# 4__eth1.net
KiCad netlist of a schematic drawn in Altium Designer
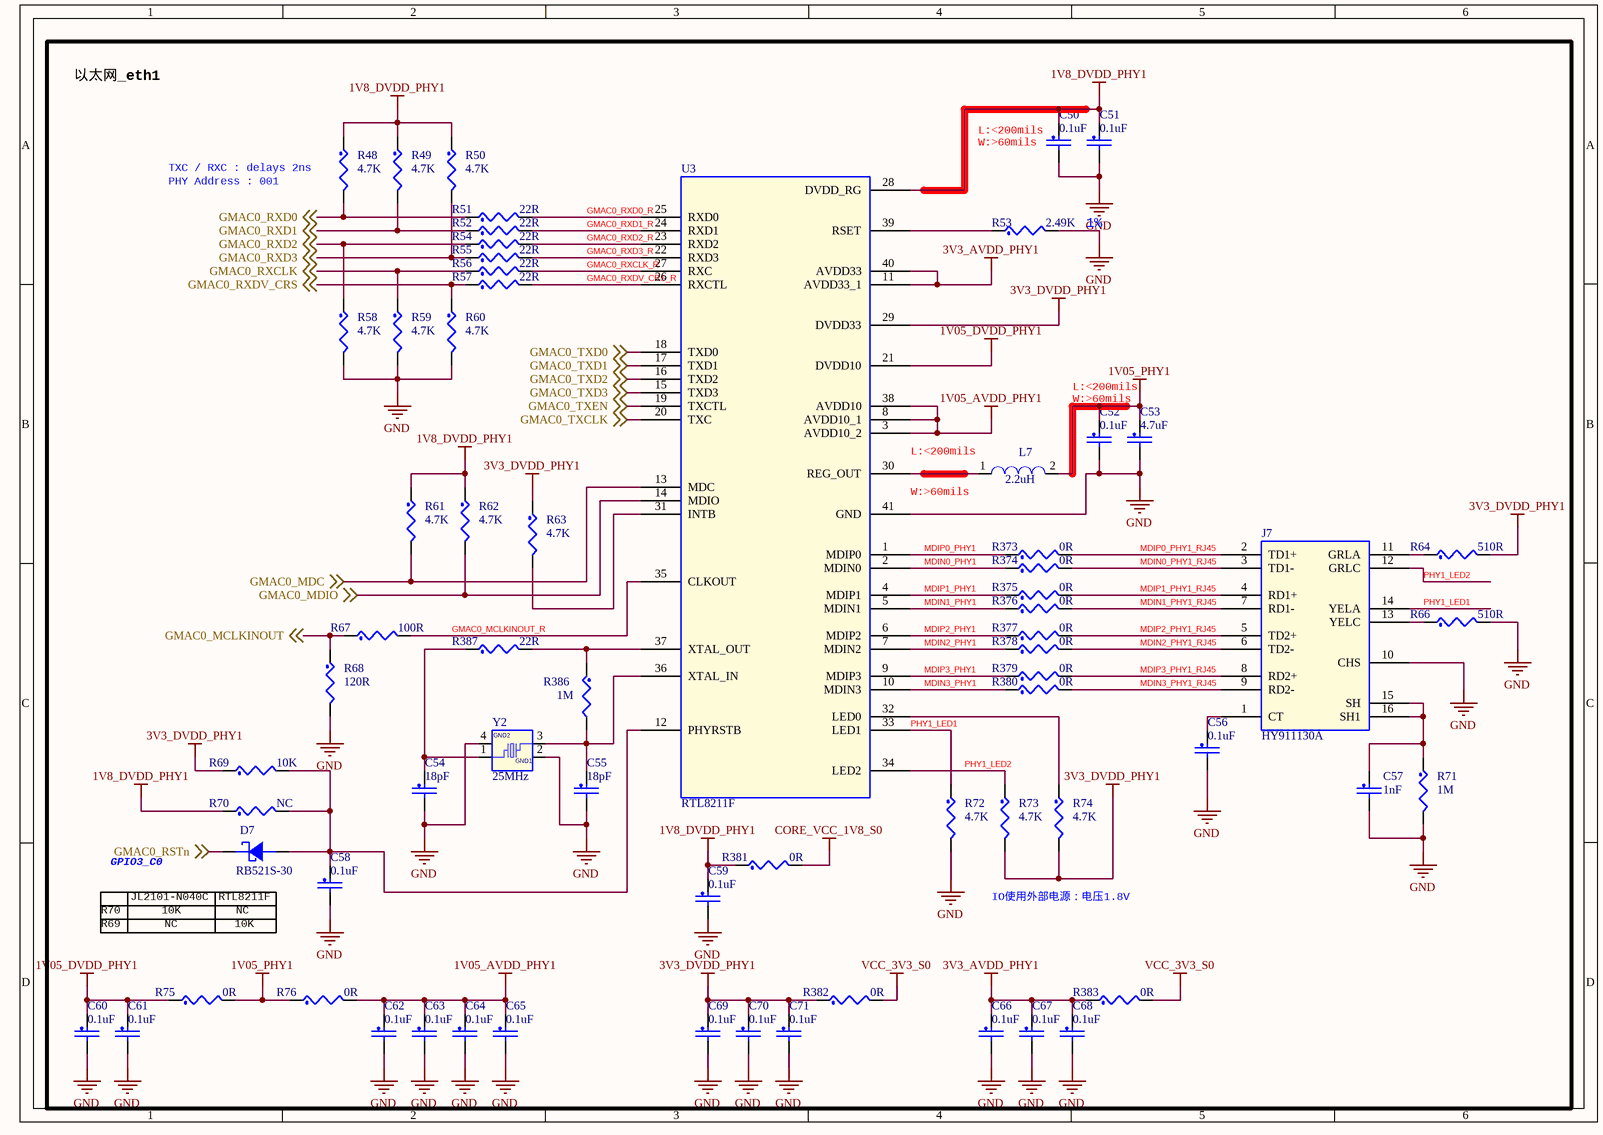
[diagram p0: 4.以太网_eth1.SchDoc]

(export (version "E")
  (design (tool "Eeschema 10.0.6"))
  (components
    (comp (ref "C50") (value "0.1uF") (footprint "0.PCB1:C0402") (libsource (lib "RK3588底板") (part "CAP_NP")))
    (comp (ref "C51") (value "0.1uF") (footprint "0.PCB1:C0402") (libsource (lib "RK3588底板") (part "CAP_NP")))
    (comp (ref "C52") (value "0.1uF") (footprint "0.PCB1:C0402") (libsource (lib "RK3588底板") (part "CAP_NP")))
    (comp (ref "C53") (value "4.7uF") (footprint "0.PCB1:C0402") (libsource (lib "RK3588底板") (part "CAP_NP")))
    (comp (ref "C54") (value "18pF") (footprint "0.PCB1:C0402") (libsource (lib "RK3588底板") (part "CAP_NP")))
    (comp (ref "C55") (value "18pF") (footprint "0.PCB1:C0402") (libsource (lib "RK3588底板") (part "CAP_NP")))
    (comp (ref "C56") (value "0.1uF") (footprint "0.PCB1:C0402") (libsource (lib "RK3588底板") (part "CAP_NP")))
    (comp (ref "C57") (value "1nF") (footprint "0.PCB1:C0805") (libsource (lib "RK3588底板") (part "CAP_NP")))
    (comp (ref "C58") (value "0.1uF") (footprint "0.PCB1:C0402") (libsource (lib "RK3588底板") (part "CAP_NP")))
    (comp (ref "C59") (value "0.1uF") (footprint "0.PCB1:C0402") (libsource (lib "RK3588底板") (part "CAP_NP")))
    (comp (ref "C60") (value "0.1uF") (footprint "0.PCB1:C0402") (libsource (lib "RK3588底板") (part "CAP_NP")))
    (comp (ref "C61") (value "0.1uF") (footprint "0.PCB1:C0402") (libsource (lib "RK3588底板") (part "CAP_NP")))
    (comp (ref "C62") (value "0.1uF") (footprint "0.PCB1:C0402") (libsource (lib "RK3588底板") (part "CAP_NP")))
    (comp (ref "C63") (value "0.1uF") (footprint "0.PCB1:C0402") (libsource (lib "RK3588底板") (part "CAP_NP")))
    (comp (ref "C64") (value "0.1uF") (footprint "0.PCB1:C0402") (libsource (lib "RK3588底板") (part "CAP_NP")))
    (comp (ref "C65") (value "0.1uF") (footprint "0.PCB1:C0402") (libsource (lib "RK3588底板") (part "CAP_NP")))
    (comp (ref "C66") (value "0.1uF") (footprint "0.PCB1:C0402") (libsource (lib "RK3588底板") (part "CAP_NP")))
    (comp (ref "C67") (value "0.1uF") (footprint "0.PCB1:C0402") (libsource (lib "RK3588底板") (part "CAP_NP")))
    (comp (ref "C68") (value "0.1uF") (footprint "0.PCB1:C0402") (libsource (lib "RK3588底板") (part "CAP_NP")))
    (comp (ref "C69") (value "0.1uF") (footprint "0.PCB1:C0402") (libsource (lib "RK3588底板") (part "CAP_NP")))
    (comp (ref "C70") (value "0.1uF") (footprint "0.PCB1:C0402") (libsource (lib "RK3588底板") (part "CAP_NP")))
    (comp (ref "C71") (value "0.1uF") (footprint "0.PCB1:C0402") (libsource (lib "RK3588底板") (part "CAP_NP")))
    (comp (ref "D7")
      (value "RB521S-30")
      (footprint "0.PCB1:SOD523")
      (libsource (lib "RK3588底板") (part "DIODE_SCHTKY"))
    )
    (comp (ref "J7")
      (value "HY911130A")
      (footprint "0.PCB1:HY911130A")
      (libsource (lib "RK3588底板") (part "HY911130A"))
    )
    (comp (ref "L7") (value "2.2uH") (footprint "0.PCB1:L2520") (libsource (lib "RK3588底板") (part "IND")))
    (comp (ref "R48") (value "4.7K") (footprint "0.PCB1:R0402") (libsource (lib "RK3588底板") (part "RES")))
    (comp (ref "R49") (value "4.7K") (footprint "0.PCB1:R0402") (libsource (lib "RK3588底板") (part "RES")))
    (comp (ref "R50") (value "4.7K") (footprint "0.PCB1:R0402") (libsource (lib "RK3588底板") (part "RES")))
    (comp (ref "R51") (value "22R") (footprint "0.PCB1:R0402") (libsource (lib "RK3588底板") (part "RES")))
    (comp (ref "R52") (value "22R") (footprint "0.PCB1:R0402") (libsource (lib "RK3588底板") (part "RES")))
    (comp (ref "R53") (value "2.49K") (footprint "0.PCB1:R0402") (libsource (lib "RK3588底板") (part "RES")))
    (comp (ref "R54") (value "22R") (footprint "0.PCB1:R0402") (libsource (lib "RK3588底板") (part "RES")))
    (comp (ref "R55") (value "22R") (footprint "0.PCB1:R0402") (libsource (lib "RK3588底板") (part "RES")))
    (comp (ref "R56") (value "22R") (footprint "0.PCB1:R0402") (libsource (lib "RK3588底板") (part "RES")))
    (comp (ref "R57") (value "22R") (footprint "0.PCB1:R0402") (libsource (lib "RK3588底板") (part "RES")))
    (comp (ref "R58") (value "4.7K") (footprint "0.PCB1:R0402") (libsource (lib "RK3588底板") (part "RES")))
    (comp (ref "R59") (value "4.7K") (footprint "0.PCB1:R0402") (libsource (lib "RK3588底板") (part "RES")))
    (comp (ref "R60") (value "4.7K") (footprint "0.PCB1:R0402") (libsource (lib "RK3588底板") (part "RES")))
    (comp (ref "R61") (value "4.7K") (footprint "0.PCB1:R0402") (libsource (lib "RK3588底板") (part "RES")))
    (comp (ref "R62") (value "4.7K") (footprint "0.PCB1:R0402") (libsource (lib "RK3588底板") (part "RES")))
    (comp (ref "R63") (value "4.7K") (footprint "0.PCB1:R0402") (libsource (lib "RK3588底板") (part "RES")))
    (comp (ref "R64") (value "510R") (footprint "0.PCB1:R0603") (libsource (lib "RK3588底板") (part "RES")))
    (comp (ref "R66") (value "510R") (footprint "0.PCB1:R0603") (libsource (lib "RK3588底板") (part "RES")))
    (comp (ref "R67") (value "100R") (footprint "0.PCB1:R0402") (libsource (lib "RK3588底板") (part "RES")))
    (comp (ref "R68") (value "120R") (footprint "0.PCB1:R0402") (libsource (lib "RK3588底板") (part "RES")))
    (comp (ref "R69") (value "10K") (footprint "0.PCB1:R0402") (libsource (lib "RK3588底板") (part "RES")))
    (comp (ref "R70") (value "NC") (footprint "0.PCB1:R0402") (libsource (lib "RK3588底板") (part "RES")))
    (comp (ref "R71") (value "1M") (footprint "0.PCB1:R0805") (libsource (lib "RK3588底板") (part "RES")))
    (comp (ref "R72") (value "4.7K") (footprint "0.PCB1:R0402") (libsource (lib "RK3588底板") (part "RES")))
    (comp (ref "R73") (value "4.7K") (footprint "0.PCB1:R0402") (libsource (lib "RK3588底板") (part "RES")))
    (comp (ref "R74") (value "4.7K") (footprint "0.PCB1:R0402") (libsource (lib "RK3588底板") (part "RES")))
    (comp (ref "R75") (value "0R") (footprint "0.PCB1:R0402") (libsource (lib "RK3588底板") (part "RES")))
    (comp (ref "R76") (value "0R") (footprint "0.PCB1:R0402") (libsource (lib "RK3588底板") (part "RES")))
    (comp (ref "R373") (value "0R") (footprint "0.PCB1:R0201") (libsource (lib "RK3588底板") (part "RES")))
    (comp (ref "R374") (value "0R") (footprint "0.PCB1:R0201") (libsource (lib "RK3588底板") (part "RES")))
    (comp (ref "R375") (value "0R") (footprint "0.PCB1:R0201") (libsource (lib "RK3588底板") (part "RES")))
    (comp (ref "R376") (value "0R") (footprint "0.PCB1:R0201") (libsource (lib "RK3588底板") (part "RES")))
    (comp (ref "R377") (value "0R") (footprint "0.PCB1:R0201") (libsource (lib "RK3588底板") (part "RES")))
    (comp (ref "R378") (value "0R") (footprint "0.PCB1:R0201") (libsource (lib "RK3588底板") (part "RES")))
    (comp (ref "R379") (value "0R") (footprint "0.PCB1:R0201") (libsource (lib "RK3588底板") (part "RES")))
    (comp (ref "R380") (value "0R") (footprint "0.PCB1:R0201") (libsource (lib "RK3588底板") (part "RES")))
    (comp (ref "R381") (value "0R") (footprint "0.PCB1:R0402") (libsource (lib "RK3588底板") (part "RES")))
    (comp (ref "R382") (value "0R") (footprint "0.PCB1:R0402") (libsource (lib "RK3588底板") (part "RES")))
    (comp (ref "R383") (value "0R") (footprint "0.PCB1:R0402") (libsource (lib "RK3588底板") (part "RES")))
    (comp (ref "R386") (value "1M") (footprint "0.PCB1:R0402") (libsource (lib "RK3588底板") (part "RES")))
    (comp (ref "R387") (value "22R") (footprint "0.PCB1:R0402") (libsource (lib "RK3588底板") (part "RES")))
    (comp (ref "U3")
      (value "RTL8211F")
      (footprint "0.PCB1:qfp_40p_r")
      (libsource (lib "RK3588底板") (part "RTL8211F"))
    )
    (comp (ref "Y2")
      (value "25MHz")
      (footprint "0.PCB1:3225")
      (libsource (lib "RK3588底板") (part "CRYSTAL_4P"))
    )
  )
  (nets
    (net (code "1") (name "/GMAC0_MCLKINOUT_R") (class "Default")
      (node (ref "R67") (pin "2") (pinfunction "2_2") (pintype "passive"))
      (node (ref "U3") (pin "35") (pinfunction "CLKOUT_35") (pintype "passive"))
    )
    (net (code "2") (name "/GMAC0_RXCLK_R") (class "Default")
      (node (ref "R56") (pin "2") (pinfunction "2_2") (pintype "passive"))
      (node (ref "U3") (pin "27") (pinfunction "RXC_27") (pintype "passive"))
    )
    (net (code "3") (name "/GMAC0_RXD0_R") (class "Default")
      (node (ref "R51") (pin "2") (pinfunction "2_2") (pintype "passive"))
      (node (ref "U3") (pin "25") (pinfunction "RXD0_25") (pintype "passive"))
    )
    (net (code "4") (name "/GMAC0_RXD1_R") (class "Default")
      (node (ref "R52") (pin "2") (pinfunction "2_2") (pintype "passive"))
      (node (ref "U3") (pin "24") (pinfunction "RXD1_24") (pintype "passive"))
    )
    (net (code "5") (name "/GMAC0_RXD2_R") (class "Default")
      (node (ref "R54") (pin "2") (pinfunction "2_2") (pintype "passive"))
      (node (ref "U3") (pin "23") (pinfunction "RXD2_23") (pintype "passive"))
    )
    (net (code "6") (name "/GMAC0_RXD3_R") (class "Default")
      (node (ref "R55") (pin "2") (pinfunction "2_2") (pintype "passive"))
      (node (ref "U3") (pin "22") (pinfunction "RXD3_22") (pintype "passive"))
    )
    (net (code "7") (name "/GMAC0_RXDV_CRS_R") (class "Default")
      (node (ref "R57") (pin "2") (pinfunction "2_2") (pintype "passive"))
      (node (ref "U3") (pin "26") (pinfunction "RXCTL_26") (pintype "passive"))
    )
    (net (code "8") (name "/MDIN0_PHY1") (class "Default")
      (node (ref "R374") (pin "1") (pinfunction "1_1") (pintype "passive"))
      (node (ref "U3") (pin "2") (pinfunction "MDIN0_2") (pintype "passive"))
    )
    (net (code "9") (name "/MDIN0_PHY1_RJ45") (class "Default")
      (node (ref "J7") (pin "3") (pinfunction "TD1-_3") (pintype "passive"))
      (node (ref "R374") (pin "2") (pinfunction "2_2") (pintype "passive"))
    )
    (net (code "10") (name "/MDIN1_PHY1") (class "Default")
      (node (ref "R376") (pin "1") (pinfunction "1_1") (pintype "passive"))
      (node (ref "U3") (pin "5") (pinfunction "MDIN1_5") (pintype "passive"))
    )
    (net (code "11") (name "/MDIN1_PHY1_RJ45") (class "Default")
      (node (ref "J7") (pin "7") (pinfunction "RD1-_7") (pintype "passive"))
      (node (ref "R376") (pin "2") (pinfunction "2_2") (pintype "passive"))
    )
    (net (code "12") (name "/MDIN2_PHY1") (class "Default")
      (node (ref "R378") (pin "1") (pinfunction "1_1") (pintype "passive"))
      (node (ref "U3") (pin "7") (pinfunction "MDIN2_7") (pintype "passive"))
    )
    (net (code "13") (name "/MDIN2_PHY1_RJ45") (class "Default")
      (node (ref "J7") (pin "6") (pinfunction "TD2-_6") (pintype "passive"))
      (node (ref "R378") (pin "2") (pinfunction "2_2") (pintype "passive"))
    )
    (net (code "14") (name "/MDIN3_PHY1") (class "Default")
      (node (ref "R380") (pin "1") (pinfunction "1_1") (pintype "passive"))
      (node (ref "U3") (pin "10") (pinfunction "MDIN3_10") (pintype "passive"))
    )
    (net (code "15") (name "/MDIN3_PHY1_RJ45") (class "Default")
      (node (ref "J7") (pin "9") (pinfunction "RD2-_9") (pintype "passive"))
      (node (ref "R380") (pin "2") (pinfunction "2_2") (pintype "passive"))
    )
    (net (code "16") (name "/MDIP0_PHY1") (class "Default")
      (node (ref "R373") (pin "1") (pinfunction "1_1") (pintype "passive"))
      (node (ref "U3") (pin "1") (pinfunction "MDIP0_1") (pintype "passive"))
    )
    (net (code "17") (name "/MDIP0_PHY1_RJ45") (class "Default")
      (node (ref "J7") (pin "2") (pinfunction "TD1+_2") (pintype "passive"))
      (node (ref "R373") (pin "2") (pinfunction "2_2") (pintype "passive"))
    )
    (net (code "18") (name "/MDIP1_PHY1") (class "Default")
      (node (ref "R375") (pin "1") (pinfunction "1_1") (pintype "passive"))
      (node (ref "U3") (pin "4") (pinfunction "MDIP1_4") (pintype "passive"))
    )
    (net (code "19") (name "/MDIP1_PHY1_RJ45") (class "Default")
      (node (ref "J7") (pin "4") (pinfunction "RD1+_4") (pintype "passive"))
      (node (ref "R375") (pin "2") (pinfunction "2_2") (pintype "passive"))
    )
    (net (code "20") (name "/MDIP2_PHY1") (class "Default")
      (node (ref "R377") (pin "1") (pinfunction "1_1") (pintype "passive"))
      (node (ref "U3") (pin "6") (pinfunction "MDIP2_6") (pintype "passive"))
    )
    (net (code "21") (name "/MDIP2_PHY1_RJ45") (class "Default")
      (node (ref "J7") (pin "5") (pinfunction "TD2+_5") (pintype "passive"))
      (node (ref "R377") (pin "2") (pinfunction "2_2") (pintype "passive"))
    )
    (net (code "22") (name "/MDIP3_PHY1") (class "Default")
      (node (ref "R379") (pin "1") (pinfunction "1_1") (pintype "passive"))
      (node (ref "U3") (pin "9") (pinfunction "MDIP3_9") (pintype "passive"))
    )
    (net (code "23") (name "/MDIP3_PHY1_RJ45") (class "Default")
      (node (ref "J7") (pin "8") (pinfunction "RD2+_8") (pintype "passive"))
      (node (ref "R379") (pin "2") (pinfunction "2_2") (pintype "passive"))
    )
    (net (code "24") (name "/PHY1_LED1") (class "Default")
      (node (ref "J7") (pin "14") (pinfunction "YELA_14") (pintype "passive"))
      (node (ref "R72") (pin "1") (pinfunction "1_1") (pintype "passive"))
      (node (ref "U3") (pin "33") (pinfunction "LED1_33") (pintype "passive"))
    )
    (net (code "25") (name "/PHY1_LED2") (class "Default")
      (node (ref "J7") (pin "12") (pinfunction "GRLC_12") (pintype "passive"))
      (node (ref "R73") (pin "1") (pinfunction "1_1") (pintype "passive"))
      (node (ref "U3") (pin "34") (pinfunction "LED2_34") (pintype "passive"))
    )
    (net (code "26") (name "1V05_AVDD_PHY1") (class "Default")
      (node (ref "C62") (pin "1") (pinfunction "1_1") (pintype "passive"))
      (node (ref "C63") (pin "1") (pinfunction "1_1") (pintype "passive"))
      (node (ref "C64") (pin "1") (pinfunction "1_1") (pintype "passive"))
      (node (ref "C65") (pin "1") (pinfunction "1_1") (pintype "passive"))
      (node (ref "R76") (pin "2") (pinfunction "2_2") (pintype "passive"))
      (node (ref "U3") (pin "3") (pinfunction "AVDD10_2_3") (pintype "passive"))
      (node (ref "U3") (pin "38") (pinfunction "AVDD10_38") (pintype "passive"))
      (node (ref "U3") (pin "8") (pinfunction "AVDD10_1_8") (pintype "passive"))
    )
    (net (code "27") (name "1V05_DVDD_PHY1") (class "Default")
      (node (ref "C60") (pin "1") (pinfunction "1_1") (pintype "passive"))
      (node (ref "C61") (pin "1") (pinfunction "1_1") (pintype "passive"))
      (node (ref "R75") (pin "1") (pinfunction "1_1") (pintype "passive"))
      (node (ref "U3") (pin "21") (pinfunction "DVDD10_21") (pintype "passive"))
    )
    (net (code "28") (name "1V05_PHY1") (class "Default")
      (node (ref "C52") (pin "1") (pinfunction "1_1") (pintype "passive"))
      (node (ref "C53") (pin "1") (pinfunction "1_1") (pintype "passive"))
      (node (ref "L7") (pin "2") (pinfunction "2_2") (pintype "passive"))
      (node (ref "R75") (pin "2") (pinfunction "2_2") (pintype "passive"))
      (node (ref "R76") (pin "1") (pinfunction "1_1") (pintype "passive"))
    )
    (net (code "29") (name "1V8_DVDD_PHY1") (class "Default")
      (node (ref "C50") (pin "1") (pinfunction "1_1") (pintype "passive"))
      (node (ref "C51") (pin "1") (pinfunction "1_1") (pintype "passive"))
      (node (ref "C59") (pin "1") (pinfunction "1_1") (pintype "passive"))
      (node (ref "R381") (pin "1") (pinfunction "1_1") (pintype "passive"))
      (node (ref "R48") (pin "1") (pinfunction "1_1") (pintype "passive"))
      (node (ref "R49") (pin "1") (pinfunction "1_1") (pintype "passive"))
      (node (ref "R50") (pin "1") (pinfunction "1_1") (pintype "passive"))
      (node (ref "R61") (pin "1") (pinfunction "1_1") (pintype "passive"))
      (node (ref "R62") (pin "1") (pinfunction "1_1") (pintype "passive"))
      (node (ref "R70") (pin "1") (pinfunction "1_1") (pintype "passive"))
      (node (ref "U3") (pin "28") (pinfunction "DVDD_RG_28") (pintype "passive"))
    )
    (net (code "30") (name "3V3_AVDD_PHY1") (class "Default")
      (node (ref "C66") (pin "1") (pinfunction "1_1") (pintype "passive"))
      (node (ref "C67") (pin "1") (pinfunction "1_1") (pintype "passive"))
      (node (ref "C68") (pin "1") (pinfunction "1_1") (pintype "passive"))
      (node (ref "R383") (pin "1") (pinfunction "1_1") (pintype "passive"))
      (node (ref "U3") (pin "11") (pinfunction "AVDD33_1_11") (pintype "passive"))
      (node (ref "U3") (pin "40") (pinfunction "AVDD33_40") (pintype "passive"))
    )
    (net (code "31") (name "3V3_DVDD_PHY1") (class "Default")
      (node (ref "C69") (pin "1") (pinfunction "1_1") (pintype "passive"))
      (node (ref "C70") (pin "1") (pinfunction "1_1") (pintype "passive"))
      (node (ref "C71") (pin "1") (pinfunction "1_1") (pintype "passive"))
      (node (ref "R382") (pin "1") (pinfunction "1_1") (pintype "passive"))
      (node (ref "R63") (pin "1") (pinfunction "1_1") (pintype "passive"))
      (node (ref "R64") (pin "2") (pinfunction "2_2") (pintype "passive"))
      (node (ref "R69") (pin "1") (pinfunction "1_1") (pintype "passive"))
      (node (ref "R73") (pin "2") (pinfunction "2_2") (pintype "passive"))
      (node (ref "R74") (pin "2") (pinfunction "2_2") (pintype "passive"))
      (node (ref "U3") (pin "29") (pinfunction "DVDD33_29") (pintype "passive"))
    )
    (net (code "32") (name "CORE_VCC_1V8_S0") (class "Default")
      (node (ref "R381") (pin "2") (pinfunction "2_2") (pintype "passive"))
    )
    (net (code "33") (name "GMAC0_MCLKINOUT") (class "Default")
      (node (ref "R67") (pin "1") (pinfunction "1_1") (pintype "passive"))
      (node (ref "R68") (pin "1") (pinfunction "1_1") (pintype "passive"))
    )
    (net (code "34") (name "GMAC0_MDC") (class "Default")
      (node (ref "R61") (pin "2") (pinfunction "2_2") (pintype "passive"))
      (node (ref "U3") (pin "13") (pinfunction "MDC_13") (pintype "passive"))
    )
    (net (code "35") (name "GMAC0_MDIO") (class "Default")
      (node (ref "R62") (pin "2") (pinfunction "2_2") (pintype "passive"))
      (node (ref "U3") (pin "14") (pinfunction "MDIO_14") (pintype "passive"))
    )
    (net (code "36") (name "GMAC0_RSTn") (class "Default")
      (node (ref "D7") (pin "1") (pinfunction "1_1") (pintype "passive"))
    )
    (net (code "37") (name "GMAC0_RXCLK") (class "Default")
      (node (ref "R56") (pin "1") (pinfunction "1_1") (pintype "passive"))
      (node (ref "R59") (pin "1") (pinfunction "1_1") (pintype "passive"))
    )
    (net (code "38") (name "GMAC0_RXD0") (class "Default")
      (node (ref "R48") (pin "2") (pinfunction "2_2") (pintype "passive"))
      (node (ref "R51") (pin "1") (pinfunction "1_1") (pintype "passive"))
    )
    (net (code "39") (name "GMAC0_RXD1") (class "Default")
      (node (ref "R49") (pin "2") (pinfunction "2_2") (pintype "passive"))
      (node (ref "R52") (pin "1") (pinfunction "1_1") (pintype "passive"))
    )
    (net (code "40") (name "GMAC0_RXD2") (class "Default")
      (node (ref "R54") (pin "1") (pinfunction "1_1") (pintype "passive"))
      (node (ref "R58") (pin "1") (pinfunction "1_1") (pintype "passive"))
    )
    (net (code "41") (name "GMAC0_RXD3") (class "Default")
      (node (ref "R50") (pin "2") (pinfunction "2_2") (pintype "passive"))
      (node (ref "R55") (pin "1") (pinfunction "1_1") (pintype "passive"))
    )
    (net (code "42") (name "GMAC0_RXDV_CRS") (class "Default")
      (node (ref "R57") (pin "1") (pinfunction "1_1") (pintype "passive"))
      (node (ref "R60") (pin "1") (pinfunction "1_1") (pintype "passive"))
    )
    (net (code "43") (name "GMAC0_TXCLK") (class "Default")
      (node (ref "U3") (pin "20") (pinfunction "TXC_20") (pintype "passive"))
    )
    (net (code "44") (name "GMAC0_TXD0") (class "Default")
      (node (ref "U3") (pin "18") (pinfunction "TXD0_18") (pintype "passive"))
    )
    (net (code "45") (name "GMAC0_TXD1") (class "Default")
      (node (ref "U3") (pin "17") (pinfunction "TXD1_17") (pintype "passive"))
    )
    (net (code "46") (name "GMAC0_TXD2") (class "Default")
      (node (ref "U3") (pin "16") (pinfunction "TXD2_16") (pintype "passive"))
    )
    (net (code "47") (name "GMAC0_TXD3") (class "Default")
      (node (ref "U3") (pin "15") (pinfunction "TXD3_15") (pintype "passive"))
    )
    (net (code "48") (name "GMAC0_TXEN") (class "Default")
      (node (ref "U3") (pin "19") (pinfunction "TXCTL_19") (pintype "passive"))
    )
    (net (code "49") (name "GND") (class "Default")
      (node (ref "C50") (pin "2") (pinfunction "2_2") (pintype "passive"))
      (node (ref "C51") (pin "2") (pinfunction "2_2") (pintype "passive"))
      (node (ref "C52") (pin "2") (pinfunction "2_2") (pintype "passive"))
      (node (ref "C53") (pin "2") (pinfunction "2_2") (pintype "passive"))
      (node (ref "C54") (pin "2") (pinfunction "2_2") (pintype "passive"))
      (node (ref "C55") (pin "2") (pinfunction "2_2") (pintype "passive"))
      (node (ref "C56") (pin "2") (pinfunction "2_2") (pintype "passive"))
      (node (ref "C57") (pin "2") (pinfunction "2_2") (pintype "passive"))
      (node (ref "C58") (pin "2") (pinfunction "2_2") (pintype "passive"))
      (node (ref "C59") (pin "2") (pinfunction "2_2") (pintype "passive"))
      (node (ref "C60") (pin "2") (pinfunction "2_2") (pintype "passive"))
      (node (ref "C61") (pin "2") (pinfunction "2_2") (pintype "passive"))
      (node (ref "C62") (pin "2") (pinfunction "2_2") (pintype "passive"))
      (node (ref "C63") (pin "2") (pinfunction "2_2") (pintype "passive"))
      (node (ref "C64") (pin "2") (pinfunction "2_2") (pintype "passive"))
      (node (ref "C65") (pin "2") (pinfunction "2_2") (pintype "passive"))
      (node (ref "C66") (pin "2") (pinfunction "2_2") (pintype "passive"))
      (node (ref "C67") (pin "2") (pinfunction "2_2") (pintype "passive"))
      (node (ref "C68") (pin "2") (pinfunction "2_2") (pintype "passive"))
      (node (ref "C69") (pin "2") (pinfunction "2_2") (pintype "passive"))
      (node (ref "C70") (pin "2") (pinfunction "2_2") (pintype "passive"))
      (node (ref "C71") (pin "2") (pinfunction "2_2") (pintype "passive"))
      (node (ref "J7") (pin "10") (pinfunction "CHS_10") (pintype "passive"))
      (node (ref "R53") (pin "2") (pinfunction "2_2") (pintype "passive"))
      (node (ref "R58") (pin "2") (pinfunction "2_2") (pintype "passive"))
      (node (ref "R59") (pin "2") (pinfunction "2_2") (pintype "passive"))
      (node (ref "R60") (pin "2") (pinfunction "2_2") (pintype "passive"))
      (node (ref "R66") (pin "2") (pinfunction "2_2") (pintype "passive"))
      (node (ref "R68") (pin "2") (pinfunction "2_2") (pintype "passive"))
      (node (ref "R71") (pin "2") (pinfunction "2_2") (pintype "passive"))
      (node (ref "R72") (pin "2") (pinfunction "2_2") (pintype "passive"))
      (node (ref "U3") (pin "41") (pinfunction "GND_41") (pintype "passive"))
      (node (ref "Y2") (pin "2") (pinfunction "GND1_2") (pintype "power_in"))
      (node (ref "Y2") (pin "4") (pinfunction "GND2_4") (pintype "power_in"))
    )
    (net (code "50") (name "Net-(C54-Pad1)") (class "Default")
      (node (ref "C54") (pin "1") (pinfunction "1_1") (pintype "passive"))
      (node (ref "R387") (pin "1") (pinfunction "1_1") (pintype "passive"))
      (node (ref "Y2") (pin "1") (pinfunction "1_1") (pintype "passive"))
    )
    (net (code "51") (name "Net-(J7-CT)") (class "Default")
      (node (ref "C56") (pin "1") (pinfunction "1_1") (pintype "passive"))
      (node (ref "J7") (pin "1") (pinfunction "CT_1") (pintype "passive"))
    )
    (net (code "52") (name "Net-(J7-GRLA)") (class "Default")
      (node (ref "J7") (pin "11") (pinfunction "GRLA_11") (pintype "passive"))
      (node (ref "R64") (pin "1") (pinfunction "1_1") (pintype "passive"))
    )
    (net (code "53") (name "Net-(J7-SH)") (class "Default")
      (node (ref "C57") (pin "1") (pinfunction "1_1") (pintype "passive"))
      (node (ref "J7") (pin "15") (pinfunction "SH_15") (pintype "passive"))
      (node (ref "J7") (pin "16") (pinfunction "SH1_16") (pintype "passive"))
      (node (ref "R71") (pin "1") (pinfunction "1_1") (pintype "passive"))
    )
    (net (code "54") (name "Net-(J7-YELC)") (class "Default")
      (node (ref "J7") (pin "13") (pinfunction "YELC_13") (pintype "passive"))
      (node (ref "R66") (pin "1") (pinfunction "1_1") (pintype "passive"))
    )
    (net (code "55") (name "Net-(U3-INTB)") (class "Default")
      (node (ref "R63") (pin "2") (pinfunction "2_2") (pintype "passive"))
      (node (ref "U3") (pin "31") (pinfunction "INTB_31") (pintype "passive"))
    )
    (net (code "56") (name "Net-(U3-LED0)") (class "Default")
      (node (ref "R74") (pin "1") (pinfunction "1_1") (pintype "passive"))
      (node (ref "U3") (pin "32") (pinfunction "LED0_32") (pintype "passive"))
    )
    (net (code "57") (name "Net-(U3-PHYRSTB)") (class "Default")
      (node (ref "C58") (pin "1") (pinfunction "1_1") (pintype "passive"))
      (node (ref "D7") (pin "2") (pinfunction "2_2") (pintype "passive"))
      (node (ref "R69") (pin "2") (pinfunction "2_2") (pintype "passive"))
      (node (ref "R70") (pin "2") (pinfunction "2_2") (pintype "passive"))
      (node (ref "U3") (pin "12") (pinfunction "PHYRSTB_12") (pintype "passive"))
    )
    (net (code "58") (name "Net-(U3-REG_OUT)") (class "Default")
      (node (ref "L7") (pin "1") (pinfunction "1_1") (pintype "passive"))
      (node (ref "U3") (pin "30") (pinfunction "REG_OUT_30") (pintype "passive"))
    )
    (net (code "59") (name "Net-(U3-RSET)") (class "Default")
      (node (ref "R53") (pin "1") (pinfunction "1_1") (pintype "passive"))
      (node (ref "U3") (pin "39") (pinfunction "RSET_39") (pintype "passive"))
    )
    (net (code "60") (name "Net-(U3-XTAL_IN)") (class "Default")
      (node (ref "C55") (pin "1") (pinfunction "1_1") (pintype "passive"))
      (node (ref "R386") (pin "2") (pinfunction "2_2") (pintype "passive"))
      (node (ref "U3") (pin "36") (pinfunction "XTAL_IN_36") (pintype "passive"))
      (node (ref "Y2") (pin "3") (pinfunction "3_3") (pintype "passive"))
    )
    (net (code "61") (name "Net-(U3-XTAL_OUT)") (class "Default")
      (node (ref "R386") (pin "1") (pinfunction "1_1") (pintype "passive"))
      (node (ref "R387") (pin "2") (pinfunction "2_2") (pintype "passive"))
      (node (ref "U3") (pin "37") (pinfunction "XTAL_OUT_37") (pintype "passive"))
    )
    (net (code "62") (name "VCC_3V3_S0") (class "Default")
      (node (ref "R382") (pin "2") (pinfunction "2_2") (pintype "passive"))
      (node (ref "R383") (pin "2") (pinfunction "2_2") (pintype "passive"))
    )
  )
)
